# SRA_20_V8_7.net
KiCad netlist of a schematic drawn in EAGLE
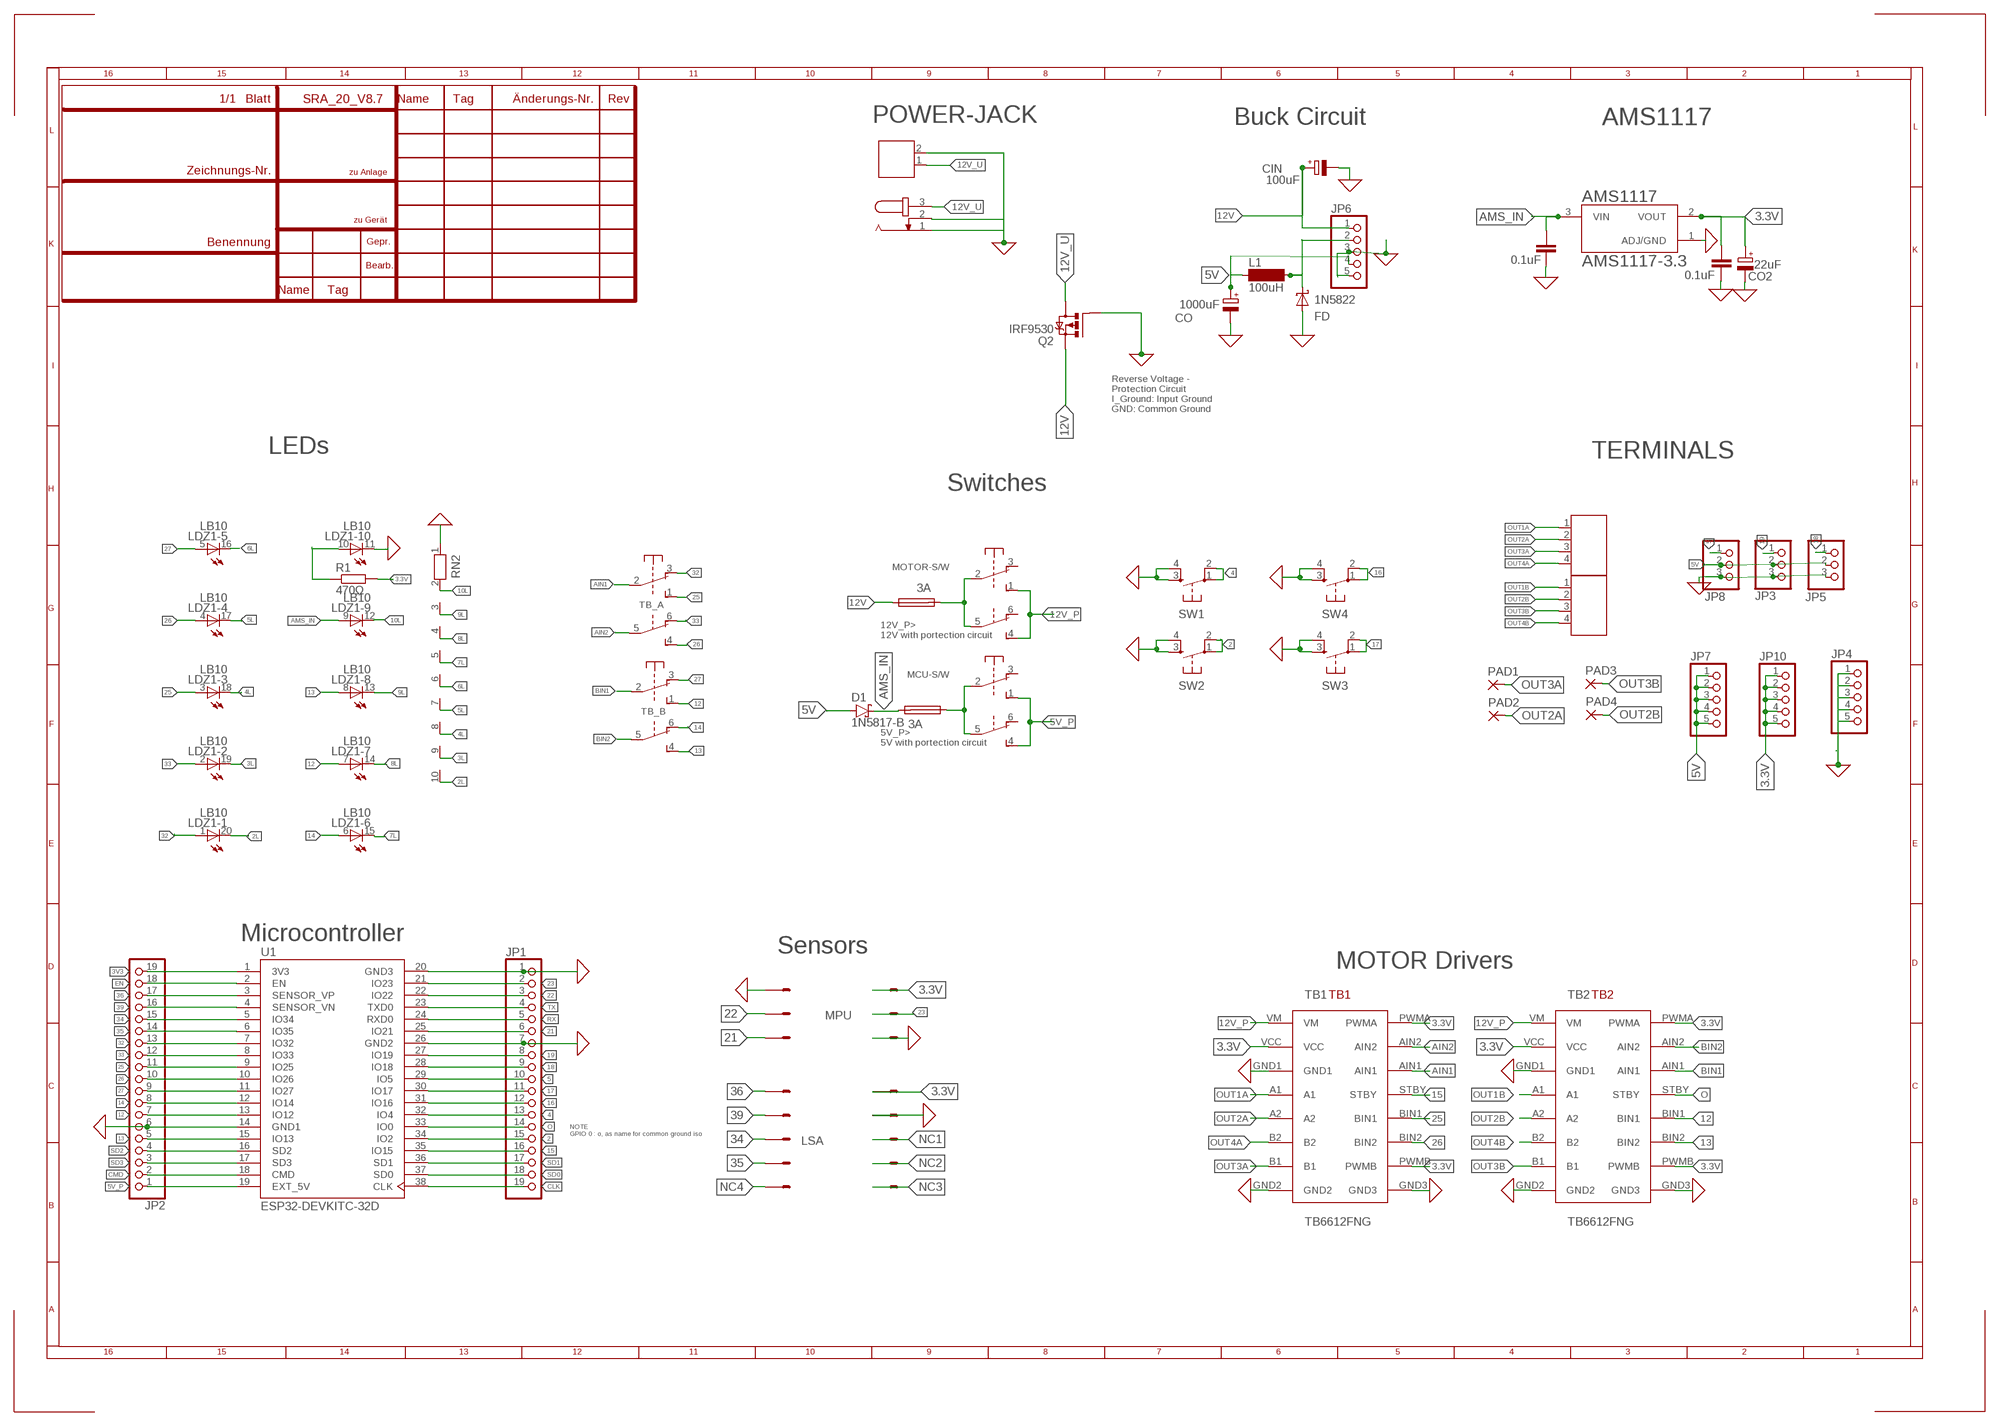
[diagram p0: schematic, sheet 1]

(export (version "E")
  (design (tool "Eeschema 10.0.6"))
  (components
    (comp (ref "12V")
      (value "691131710002")
      (footprint "eagle-import:691131710002")
      (libsource (lib "eagle-import") (part "691131710002"))
    )
    (comp (ref "AMS1117")
      (value "AMS1117-3.3")
      (footprint "eagle-import:SOT229P700X180-4N")
      (fields (field (name "MF") "Advanced Monolithic Systems"))
      (libsource (lib "eagle-import") (part "AMS1117-3.3"))
    )
    (comp (ref "CIN")
      (value "100uF")
      (footprint "eagle-import:E2,5-6")
      (libsource (lib "eagle-import") (part "CPOL-EUE2.5-6"))
    )
    (comp (ref "CIN1")
      (value "0.1uF")
      (footprint "eagle-import:C5B2.5")
      (libsource (lib "eagle-import") (part "C5/2.5"))
    )
    (comp (ref "CO")
      (value "1000uF")
      (footprint "eagle-import:E3,5-10")
      (libsource (lib "eagle-import") (part "CPOL-EUE3.5-10"))
    )
    (comp (ref "CO1")
      (value "0.1uF")
      (footprint "eagle-import:C5B2.5")
      (libsource (lib "eagle-import") (part "C5/2.5"))
    )
    (comp (ref "CO2")
      (value "22uF")
      (footprint "eagle-import:E2,5-6")
      (libsource (lib "eagle-import") (part "CPOL-EUE2.5-6"))
    )
    (comp (ref "D1")
      (value "1N5817-B")
      (footprint "eagle-import:DO41-7.6")
      (libsource (lib "eagle-import") (part "1N5817-B"))
    )
    (comp (ref "F2")
      (value "3A")
      (footprint "eagle-import:SH25")
      (fields (field (name "MF") "SCHURTER") (field (name "MPN") "0031.8211"))
      (libsource (lib "eagle-import") (part "SH25"))
    )
    (comp (ref "F3")
      (value "3A")
      (footprint "eagle-import:SH25")
      (fields (field (name "MF") "SCHURTER") (field (name "MPN") "0031.8211"))
      (libsource (lib "eagle-import") (part "SH25"))
    )
    (comp (ref "FD")
      (value "1N5822")
      (footprint "eagle-import:DIOAD2120W130L950D530P")
      (fields (field (name "MF") "ON Semiconductor"))
      (libsource (lib "eagle-import") (part "1N5822"))
    )
    (comp (ref "J1")
      (value "691131710004")
      (footprint "eagle-import:691131710004")
      (libsource (lib "eagle-import") (part "691131710004"))
    )
    (comp (ref "J2")
      (value "691131710004")
      (footprint "eagle-import:691131710004")
      (libsource (lib "eagle-import") (part "691131710004"))
    )
    (comp (ref "JP1")
      (value "PINHD-1X19")
      (footprint "eagle-import:1X19")
      (libsource (lib "eagle-import") (part "PINHD-1X19"))
    )
    (comp (ref "JP2")
      (value "PINHD-1X19")
      (footprint "eagle-import:1X19")
      (libsource (lib "eagle-import") (part "PINHD-1X19"))
    )
    (comp (ref "JP3")
      (value "PINHD-1X3")
      (footprint "eagle-import:1X03")
      (libsource (lib "eagle-import") (part "PINHD-1X3"))
    )
    (comp (ref "JP4")
      (value "PINHD-1X5")
      (footprint "eagle-import:1X05")
      (libsource (lib "eagle-import") (part "pinhead_2_PINHD-1X5"))
    )
    (comp (ref "JP5")
      (value "PINHD-1X3")
      (footprint "eagle-import:1X03")
      (libsource (lib "eagle-import") (part "PINHD-1X3"))
    )
    (comp (ref "JP6")
      (value "PINHD-1X5")
      (footprint "eagle-import:1X05")
      (libsource (lib "eagle-import") (part "PINHD-1X5"))
    )
    (comp (ref "JP7")
      (value "PINHD-1X5")
      (footprint "eagle-import:1X05")
      (libsource (lib "eagle-import") (part "pinhead_2_PINHD-1X5"))
    )
    (comp (ref "JP8")
      (value "PINHD-1X3")
      (footprint "eagle-import:1X03")
      (libsource (lib "eagle-import") (part "PINHD-1X3"))
    )
    (comp (ref "JP10")
      (value "PINHD-1X5")
      (footprint "eagle-import:1X05")
      (libsource (lib "eagle-import") (part "pinhead_2_PINHD-1X5"))
    )
    (comp (ref "L1")
      (value "100uH")
      (footprint "eagle-import:SD12K100")
      (libsource (lib "eagle-import") (part "SD12K100"))
    )
    (comp (ref "LDZ1")
      (value "LB10")
      (footprint "eagle-import:LB10")
      (libsource (lib "eagle-import") (part "LB10"))
    )
    (comp (ref "LINE-SENSOR")
      (value "057-010-1")
      (footprint "eagle-import:057-010-1")
      (libsource (lib "eagle-import") (part "057-010-1"))
    )
    (comp (ref "MCU-S/W")
      (value "9077-2")
      (footprint "eagle-import:9077-2")
      (libsource (lib "eagle-import") (part "9077-2"))
    )
    (comp (ref "MOTOR-S/W")
      (value "9077-2")
      (footprint "eagle-import:9077-2")
      (libsource (lib "eagle-import") (part "9077-2"))
    )
    (comp (ref "PAD1")
      (value "SMD2")
      (footprint "eagle-import:SMD1,27-2,54")
      (libsource (lib "eagle-import") (part "SMD2"))
    )
    (comp (ref "PAD2")
      (value "SMD2")
      (footprint "eagle-import:SMD1,27-2,54")
      (libsource (lib "eagle-import") (part "SMD2"))
    )
    (comp (ref "PAD3")
      (value "SMD2")
      (footprint "eagle-import:SMD1,27-2,54")
      (libsource (lib "eagle-import") (part "SMD2"))
    )
    (comp (ref "PAD4")
      (value "SMD2")
      (footprint "eagle-import:SMD1,27-2,54")
      (libsource (lib "eagle-import") (part "SMD2"))
    )
    (comp (ref "POWER-JACK")
      (value "JACK-PLUG1")
      (footprint "eagle-import:SPC4078")
      (libsource (lib "eagle-import") (part "JACK-PLUG1"))
    )
    (comp (ref "Q2")
      (value "IRF9530")
      (footprint "eagle-import:TO220BV")
      (libsource (lib "eagle-import") (part "IRF9530"))
    )
    (comp (ref "R1")
      (value "470Ω")
      (footprint "eagle-import:0204_7")
      (libsource (lib "eagle-import") (part "R-EU_0204/7"))
    )
    (comp (ref "RN2")
      (value "RN09")
      (footprint "eagle-import:RN-10")
      (libsource (lib "eagle-import") (part "RN09"))
    )
    (comp (ref "SW1")
      (value "DTS-6")
      (footprint "eagle-import:DTS-6")
      (libsource (lib "eagle-import") (part "DTS-6"))
    )
    (comp (ref "SW2")
      (value "DTS-6")
      (footprint "eagle-import:DTS-6")
      (libsource (lib "eagle-import") (part "DTS-6"))
    )
    (comp (ref "SW3")
      (value "DTS-6")
      (footprint "eagle-import:DTS-6")
      (libsource (lib "eagle-import") (part "DTS-6"))
    )
    (comp (ref "SW4")
      (value "DTS-6")
      (footprint "eagle-import:DTS-6")
      (libsource (lib "eagle-import") (part "DTS-6"))
    )
    (comp (ref "TB1")
      (value "TB6612FNG")
      (footprint "eagle-import:TB6612FNG")
      (libsource (lib "eagle-import") (part "TB6612FNG"))
    )
    (comp (ref "TB2")
      (value "TB6612FNG")
      (footprint "eagle-import:TB6612FNG")
      (libsource (lib "eagle-import") (part "TB6612FNG"))
    )
    (comp (ref "TB_A")
      (value "9077-2")
      (footprint "eagle-import:9077-2")
      (libsource (lib "eagle-import") (part "9077-2"))
    )
    (comp (ref "TB_B")
      (value "9077-2")
      (footprint "eagle-import:9077-2")
      (libsource (lib "eagle-import") (part "9077-2"))
    )
    (comp (ref "U1")
      (value "ESP32-DEVKITC-32D")
      (footprint "eagle-import:MODULE_ESP32-DEVKITC-32D")
      (fields (field (name "MF") "Espressif Systems"))
      (libsource (lib "eagle-import") (part "ESP32-DEVKITC-32D"))
    )
    (comp (ref "X1")
      (value "057-006-1")
      (footprint "eagle-import:057-006-1")
      (libsource (lib "eagle-import") (part "057-006-1"))
    )
  )
  (nets
    (net (code "1") (name "2") (class "Default")
      (node (ref "JP1") (pin "15") (pinfunction "15_15") (pintype "passive"))
      (node (ref "SW2") (pin "1") (pinfunction "1_1") (pintype "passive"))
      (node (ref "SW2") (pin "2") (pinfunction "2_2") (pintype "passive"))
      (node (ref "U1") (pin "34") (pinfunction "IO2_34") (pintype "bidirectional"))
    )
    (net (code "2") (name "2L") (class "Default")
      (node (ref "LDZ1") (pin "20") (pinfunction "C_20") (pintype "passive"))
      (node (ref "RN2") (pin "10") (pinfunction "10_10") (pintype "passive"))
    )
    (net (code "3") (name "3.3V") (class "Default")
      (node (ref "AMS1117") (pin "2") (pinfunction "VOUT_2") (pintype "output"))
      (node (ref "CO1") (pin "2") (pinfunction "2_2") (pintype "passive"))
      (node (ref "CO2") (pin "+") (pinfunction "+_+") (pintype "passive"))
      (node (ref "JP10") (pin "1") (pinfunction "1_1") (pintype "passive"))
      (node (ref "JP10") (pin "2") (pinfunction "2_2") (pintype "passive"))
      (node (ref "JP10") (pin "3") (pinfunction "3_3") (pintype "passive"))
      (node (ref "JP10") (pin "4") (pinfunction "4_4") (pintype "passive"))
      (node (ref "JP10") (pin "5") (pinfunction "5_5") (pintype "passive"))
      (node (ref "LINE-SENSOR") (pin "2") (pinfunction "S_2") (pintype "passive"))
      (node (ref "R1") (pin "2") (pinfunction "2_2") (pintype "passive"))
      (node (ref "TB1") (pin "PWMA") (pinfunction "PWMA_PWMA") (pintype "bidirectional"))
      (node (ref "TB1") (pin "PWMB") (pinfunction "PWMB_PWMB") (pintype "bidirectional"))
      (node (ref "TB1") (pin "VCC") (pinfunction "VCC_VCC") (pintype "bidirectional"))
      (node (ref "TB2") (pin "PWMA") (pinfunction "PWMA_PWMA") (pintype "bidirectional"))
      (node (ref "TB2") (pin "PWMB") (pinfunction "PWMB_PWMB") (pintype "bidirectional"))
      (node (ref "TB2") (pin "VCC") (pinfunction "VCC_VCC") (pintype "bidirectional"))
      (node (ref "X1") (pin "2") (pinfunction "S_2") (pintype "passive"))
    )
    (net (code "4") (name "3L") (class "Default")
      (node (ref "LDZ1") (pin "19") (pinfunction "C_19") (pintype "passive"))
      (node (ref "RN2") (pin "9") (pinfunction "9_9") (pintype "passive"))
    )
    (net (code "5") (name "3V3") (class "Default")
      (node (ref "JP2") (pin "19") (pinfunction "19_19") (pintype "passive"))
      (node (ref "U1") (pin "1") (pinfunction "3V3_1") (pintype "power_in"))
    )
    (net (code "6") (name "4") (class "Default")
      (node (ref "JP1") (pin "13") (pinfunction "13_13") (pintype "passive"))
      (node (ref "SW1") (pin "1") (pinfunction "1_1") (pintype "passive"))
      (node (ref "SW1") (pin "2") (pinfunction "2_2") (pintype "passive"))
      (node (ref "U1") (pin "32") (pinfunction "IO4_32") (pintype "bidirectional"))
    )
    (net (code "7") (name "4L") (class "Default")
      (node (ref "LDZ1") (pin "18") (pinfunction "C_18") (pintype "passive"))
      (node (ref "RN2") (pin "8") (pinfunction "8_8") (pintype "passive"))
    )
    (net (code "8") (name "5") (class "Default")
      (node (ref "JP1") (pin "10") (pinfunction "10_10") (pintype "passive"))
      (node (ref "JP8") (pin "1") (pinfunction "1_1") (pintype "passive"))
      (node (ref "U1") (pin "29") (pinfunction "IO5_29") (pintype "bidirectional"))
    )
    (net (code "9") (name "5L") (class "Default")
      (node (ref "LDZ1") (pin "17") (pinfunction "C_17") (pintype "passive"))
      (node (ref "RN2") (pin "7") (pinfunction "7_7") (pintype "passive"))
    )
    (net (code "10") (name "5V") (class "Default")
      (node (ref "CO") (pin "+") (pinfunction "+_+") (pintype "passive"))
      (node (ref "D1") (pin "A") (pinfunction "A_A") (pintype "passive"))
      (node (ref "JP3") (pin "2") (pinfunction "2_2") (pintype "passive"))
      (node (ref "JP5") (pin "2") (pinfunction "2_2") (pintype "passive"))
      (node (ref "JP6") (pin "4") (pinfunction "4_4") (pintype "passive"))
      (node (ref "JP7") (pin "1") (pinfunction "1_1") (pintype "passive"))
      (node (ref "JP7") (pin "2") (pinfunction "2_2") (pintype "passive"))
      (node (ref "JP7") (pin "3") (pinfunction "3_3") (pintype "passive"))
      (node (ref "JP7") (pin "4") (pinfunction "4_4") (pintype "passive"))
      (node (ref "JP7") (pin "5") (pinfunction "5_5") (pintype "passive"))
      (node (ref "JP8") (pin "2") (pinfunction "2_2") (pintype "passive"))
      (node (ref "L1") (pin "1") (pinfunction "1_1") (pintype "passive"))
    )
    (net (code "11") (name "5V_P") (class "Default")
      (node (ref "JP2") (pin "1") (pinfunction "1_1") (pintype "passive"))
      (node (ref "MCU-S/W") (pin "1") (pinfunction "S_1") (pintype "passive"))
      (node (ref "MCU-S/W") (pin "4") (pinfunction "S_4") (pintype "passive"))
      (node (ref "U1") (pin "19") (pinfunction "EXT_5V_19") (pintype "power_in"))
    )
    (net (code "12") (name "6L") (class "Default")
      (node (ref "LDZ1") (pin "16") (pinfunction "C_16") (pintype "passive"))
      (node (ref "RN2") (pin "6") (pinfunction "6_6") (pintype "passive"))
    )
    (net (code "13") (name "7L") (class "Default")
      (node (ref "LDZ1") (pin "15") (pinfunction "C_15") (pintype "passive"))
      (node (ref "RN2") (pin "5") (pinfunction "5_5") (pintype "passive"))
    )
    (net (code "14") (name "8L") (class "Default")
      (node (ref "LDZ1") (pin "14") (pinfunction "C_14") (pintype "passive"))
      (node (ref "RN2") (pin "4") (pinfunction "4_4") (pintype "passive"))
    )
    (net (code "15") (name "9L") (class "Default")
      (node (ref "LDZ1") (pin "13") (pinfunction "C_13") (pintype "passive"))
      (node (ref "RN2") (pin "3") (pinfunction "3_3") (pintype "passive"))
    )
    (net (code "16") (name "10L") (class "Default")
      (node (ref "LDZ1") (pin "12") (pinfunction "C_12") (pintype "passive"))
      (node (ref "RN2") (pin "2") (pinfunction "2_2") (pintype "passive"))
    )
    (net (code "17") (name "12") (class "Default")
      (node (ref "JP2") (pin "7") (pinfunction "7_7") (pintype "passive"))
      (node (ref "LDZ1") (pin "7") (pinfunction "A_7") (pintype "passive"))
      (node (ref "TB2") (pin "BIN1") (pinfunction "BIN1_BIN1") (pintype "bidirectional"))
      (node (ref "TB_B") (pin "1") (pinfunction "S_1") (pintype "passive"))
      (node (ref "U1") (pin "13") (pinfunction "IO12_13") (pintype "bidirectional"))
    )
    (net (code "18") (name "12V") (class "Default")
      (node (ref "CIN") (pin "+") (pinfunction "+_+") (pintype "passive"))
      (node (ref "F3") (pin "1") (pinfunction "1_1") (pintype "passive"))
      (node (ref "JP6") (pin "1") (pinfunction "1_1") (pintype "passive"))
      (node (ref "Q2") (pin "S") (pinfunction "S_S") (pintype "passive"))
    )
    (net (code "19") (name "12V_P") (class "Default")
      (node (ref "MOTOR-S/W") (pin "1") (pinfunction "S_1") (pintype "passive"))
      (node (ref "MOTOR-S/W") (pin "4") (pinfunction "S_4") (pintype "passive"))
      (node (ref "TB1") (pin "VM") (pinfunction "VM_VM") (pintype "bidirectional"))
      (node (ref "TB2") (pin "VM") (pinfunction "VM_VM") (pintype "bidirectional"))
    )
    (net (code "20") (name "12V_U") (class "Default")
      (node (ref "12V") (pin "1") (pinfunction "1_1") (pintype "passive"))
      (node (ref "POWER-JACK") (pin "3") (pinfunction "3_3") (pintype "passive"))
      (node (ref "Q2") (pin "D") (pinfunction "D_D") (pintype "passive"))
    )
    (net (code "21") (name "13") (class "Default")
      (node (ref "JP2") (pin "5") (pinfunction "5_5") (pintype "passive"))
      (node (ref "LDZ1") (pin "8") (pinfunction "A_8") (pintype "passive"))
      (node (ref "TB2") (pin "BIN2") (pinfunction "BIN2_BIN2") (pintype "bidirectional"))
      (node (ref "TB_B") (pin "4") (pinfunction "S_4") (pintype "passive"))
      (node (ref "U1") (pin "15") (pinfunction "IO13_15") (pintype "bidirectional"))
    )
    (net (code "22") (name "14") (class "Default")
      (node (ref "JP2") (pin "8") (pinfunction "8_8") (pintype "passive"))
      (node (ref "LDZ1") (pin "6") (pinfunction "A_6") (pintype "passive"))
      (node (ref "TB_B") (pin "6") (pinfunction "O_6") (pintype "passive"))
      (node (ref "U1") (pin "12") (pinfunction "IO14_12") (pintype "bidirectional"))
    )
    (net (code "23") (name "15") (class "Default")
      (node (ref "JP1") (pin "16") (pinfunction "16_16") (pintype "passive"))
      (node (ref "TB1") (pin "STBY") (pinfunction "STBY_STBY") (pintype "bidirectional"))
      (node (ref "U1") (pin "35") (pinfunction "IO15_35") (pintype "bidirectional"))
    )
    (net (code "24") (name "16") (class "Default")
      (node (ref "JP1") (pin "12") (pinfunction "12_12") (pintype "passive"))
      (node (ref "SW4") (pin "1") (pinfunction "1_1") (pintype "passive"))
      (node (ref "SW4") (pin "2") (pinfunction "2_2") (pintype "passive"))
      (node (ref "U1") (pin "31") (pinfunction "IO16_31") (pintype "bidirectional"))
    )
    (net (code "25") (name "17") (class "Default")
      (node (ref "JP1") (pin "11") (pinfunction "11_11") (pintype "passive"))
      (node (ref "SW3") (pin "1") (pinfunction "1_1") (pintype "passive"))
      (node (ref "SW3") (pin "2") (pinfunction "2_2") (pintype "passive"))
      (node (ref "U1") (pin "30") (pinfunction "IO17_30") (pintype "bidirectional"))
    )
    (net (code "26") (name "18") (class "Default")
      (node (ref "JP1") (pin "9") (pinfunction "9_9") (pintype "passive"))
      (node (ref "JP5") (pin "1") (pinfunction "1_1") (pintype "passive"))
      (node (ref "U1") (pin "28") (pinfunction "IO18_28") (pintype "bidirectional"))
    )
    (net (code "27") (name "19") (class "Default")
      (node (ref "JP1") (pin "8") (pinfunction "8_8") (pintype "passive"))
      (node (ref "JP3") (pin "1") (pinfunction "1_1") (pintype "passive"))
      (node (ref "U1") (pin "27") (pinfunction "IO19_27") (pintype "bidirectional"))
    )
    (net (code "28") (name "21") (class "Default")
      (node (ref "JP1") (pin "6") (pinfunction "6_6") (pintype "passive"))
      (node (ref "U1") (pin "25") (pinfunction "IO21_25") (pintype "bidirectional"))
      (node (ref "X1") (pin "5") (pinfunction "S_5") (pintype "passive"))
    )
    (net (code "29") (name "22") (class "Default")
      (node (ref "JP1") (pin "3") (pinfunction "3_3") (pintype "passive"))
      (node (ref "U1") (pin "22") (pinfunction "IO22_22") (pintype "bidirectional"))
      (node (ref "X1") (pin "3") (pinfunction "S_3") (pintype "passive"))
    )
    (net (code "30") (name "23") (class "Default")
      (node (ref "JP1") (pin "2") (pinfunction "2_2") (pintype "passive"))
      (node (ref "U1") (pin "21") (pinfunction "IO23_21") (pintype "bidirectional"))
      (node (ref "X1") (pin "4") (pinfunction "S_4") (pintype "passive"))
    )
    (net (code "31") (name "25") (class "Default")
      (node (ref "JP2") (pin "11") (pinfunction "11_11") (pintype "passive"))
      (node (ref "LDZ1") (pin "3") (pinfunction "A_3") (pintype "passive"))
      (node (ref "TB1") (pin "BIN1") (pinfunction "BIN1_BIN1") (pintype "bidirectional"))
      (node (ref "TB_A") (pin "1") (pinfunction "S_1") (pintype "passive"))
      (node (ref "U1") (pin "9") (pinfunction "IO25_9") (pintype "bidirectional"))
    )
    (net (code "32") (name "26") (class "Default")
      (node (ref "JP2") (pin "10") (pinfunction "10_10") (pintype "passive"))
      (node (ref "LDZ1") (pin "4") (pinfunction "A_4") (pintype "passive"))
      (node (ref "TB1") (pin "BIN2") (pinfunction "BIN2_BIN2") (pintype "bidirectional"))
      (node (ref "TB_A") (pin "4") (pinfunction "S_4") (pintype "passive"))
      (node (ref "U1") (pin "10") (pinfunction "IO26_10") (pintype "bidirectional"))
    )
    (net (code "33") (name "27") (class "Default")
      (node (ref "JP2") (pin "9") (pinfunction "9_9") (pintype "passive"))
      (node (ref "LDZ1") (pin "5") (pinfunction "A_5") (pintype "passive"))
      (node (ref "TB_B") (pin "3") (pinfunction "O_3") (pintype "passive"))
      (node (ref "U1") (pin "11") (pinfunction "IO27_11") (pintype "bidirectional"))
    )
    (net (code "34") (name "32") (class "Default")
      (node (ref "JP2") (pin "13") (pinfunction "13_13") (pintype "passive"))
      (node (ref "LDZ1") (pin "1") (pinfunction "A_1") (pintype "passive"))
      (node (ref "TB_A") (pin "3") (pinfunction "O_3") (pintype "passive"))
      (node (ref "U1") (pin "7") (pinfunction "IO32_7") (pintype "bidirectional"))
    )
    (net (code "35") (name "33") (class "Default")
      (node (ref "JP2") (pin "12") (pinfunction "12_12") (pintype "passive"))
      (node (ref "LDZ1") (pin "2") (pinfunction "A_2") (pintype "passive"))
      (node (ref "TB_A") (pin "6") (pinfunction "O_6") (pintype "passive"))
      (node (ref "U1") (pin "8") (pinfunction "IO33_8") (pintype "bidirectional"))
    )
    (net (code "36") (name "34") (class "Default")
      (node (ref "JP2") (pin "15") (pinfunction "15_15") (pintype "passive"))
      (node (ref "LINE-SENSOR") (pin "5") (pinfunction "S_5") (pintype "passive"))
      (node (ref "U1") (pin "5") (pinfunction "IO34_5") (pintype "bidirectional"))
    )
    (net (code "37") (name "35") (class "Default")
      (node (ref "JP2") (pin "14") (pinfunction "14_14") (pintype "passive"))
      (node (ref "LINE-SENSOR") (pin "7") (pinfunction "S_7") (pintype "passive"))
      (node (ref "U1") (pin "6") (pinfunction "IO35_6") (pintype "bidirectional"))
    )
    (net (code "38") (name "36") (class "Default")
      (node (ref "JP2") (pin "17") (pinfunction "17_17") (pintype "passive"))
      (node (ref "LINE-SENSOR") (pin "1") (pinfunction "S_1") (pintype "passive"))
      (node (ref "U1") (pin "3") (pinfunction "SENSOR_VP_3") (pintype "input"))
    )
    (net (code "39") (name "39") (class "Default")
      (node (ref "JP2") (pin "16") (pinfunction "16_16") (pintype "passive"))
      (node (ref "LINE-SENSOR") (pin "3") (pinfunction "S_3") (pintype "passive"))
      (node (ref "U1") (pin "4") (pinfunction "SENSOR_VN_4") (pintype "input"))
    )
    (net (code "40") (name "AIN1") (class "Default")
      (node (ref "TB1") (pin "AIN1") (pinfunction "AIN1_AIN1") (pintype "bidirectional"))
      (node (ref "TB_A") (pin "2") (pinfunction "P_2") (pintype "passive"))
    )
    (net (code "41") (name "AIN2") (class "Default")
      (node (ref "TB1") (pin "AIN2") (pinfunction "AIN2_AIN2") (pintype "bidirectional"))
      (node (ref "TB_A") (pin "5") (pinfunction "P_5") (pintype "passive"))
    )
    (net (code "42") (name "AMS_IN") (class "Default")
      (node (ref "AMS1117") (pin "3") (pinfunction "VIN_3") (pintype "input"))
      (node (ref "CIN1") (pin "2") (pinfunction "2_2") (pintype "passive"))
      (node (ref "D1") (pin "C") (pinfunction "C_C") (pintype "passive"))
      (node (ref "F2") (pin "2") (pinfunction "2_2") (pintype "passive"))
      (node (ref "LDZ1") (pin "9") (pinfunction "A_9") (pintype "passive"))
    )
    (net (code "43") (name "BIN1") (class "Default")
      (node (ref "TB2") (pin "AIN1") (pinfunction "AIN1_AIN1") (pintype "bidirectional"))
      (node (ref "TB_B") (pin "2") (pinfunction "P_2") (pintype "passive"))
    )
    (net (code "44") (name "BIN2") (class "Default")
      (node (ref "TB2") (pin "AIN2") (pinfunction "AIN2_AIN2") (pintype "bidirectional"))
      (node (ref "TB_B") (pin "5") (pinfunction "P_5") (pintype "passive"))
    )
    (net (code "45") (name "CLK") (class "Default")
      (node (ref "JP1") (pin "19") (pinfunction "19_19") (pintype "passive"))
      (node (ref "U1") (pin "38") (pinfunction "CLK_38") (pintype "input"))
    )
    (net (code "46") (name "CMD") (class "Default")
      (node (ref "JP2") (pin "2") (pinfunction "2_2") (pintype "passive"))
      (node (ref "U1") (pin "18") (pinfunction "CMD_18") (pintype "bidirectional"))
    )
    (net (code "47") (name "EN") (class "Default")
      (node (ref "JP2") (pin "18") (pinfunction "18_18") (pintype "passive"))
      (node (ref "U1") (pin "2") (pinfunction "EN_2") (pintype "input"))
    )
    (net (code "48") (name "GND") (class "Default")
      (node (ref "12V") (pin "2") (pinfunction "2_2") (pintype "passive"))
      (node (ref "AMS1117") (pin "1") (pinfunction "ADJ/GND_1") (pintype "power_in"))
      (node (ref "CIN") (pin "-") (pinfunction "-_-") (pintype "passive"))
      (node (ref "CIN1") (pin "1") (pinfunction "1_1") (pintype "passive"))
      (node (ref "CO") (pin "-") (pinfunction "-_-") (pintype "passive"))
      (node (ref "CO1") (pin "1") (pinfunction "1_1") (pintype "passive"))
      (node (ref "CO2") (pin "-") (pinfunction "-_-") (pintype "passive"))
      (node (ref "FD") (pin "A") (pinfunction "A_A") (pintype "passive"))
      (node (ref "JP1") (pin "1") (pinfunction "1_1") (pintype "passive"))
      (node (ref "JP1") (pin "7") (pinfunction "7_7") (pintype "passive"))
      (node (ref "JP2") (pin "6") (pinfunction "6_6") (pintype "passive"))
      (node (ref "JP3") (pin "3") (pinfunction "3_3") (pintype "passive"))
      (node (ref "JP4") (pin "1") (pinfunction "1_1") (pintype "passive"))
      (node (ref "JP4") (pin "2") (pinfunction "2_2") (pintype "passive"))
      (node (ref "JP4") (pin "3") (pinfunction "3_3") (pintype "passive"))
      (node (ref "JP4") (pin "4") (pinfunction "4_4") (pintype "passive"))
      (node (ref "JP4") (pin "5") (pinfunction "5_5") (pintype "passive"))
      (node (ref "JP5") (pin "3") (pinfunction "3_3") (pintype "passive"))
      (node (ref "JP6") (pin "3") (pinfunction "3_3") (pintype "passive"))
      (node (ref "JP6") (pin "5") (pinfunction "5_5") (pintype "passive"))
      (node (ref "JP8") (pin "3") (pinfunction "3_3") (pintype "passive"))
      (node (ref "LDZ1") (pin "11") (pinfunction "C_11") (pintype "passive"))
      (node (ref "LINE-SENSOR") (pin "4") (pinfunction "S_4") (pintype "passive"))
      (node (ref "POWER-JACK") (pin "1") (pinfunction "1_1") (pintype "passive"))
      (node (ref "POWER-JACK") (pin "2") (pinfunction "2_2") (pintype "passive"))
      (node (ref "Q2") (pin "G") (pinfunction "G_G") (pintype "passive"))
      (node (ref "RN2") (pin "1") (pinfunction "1_1") (pintype "passive"))
      (node (ref "SW1") (pin "3") (pinfunction "3_3") (pintype "passive"))
      (node (ref "SW1") (pin "4") (pinfunction "4_4") (pintype "passive"))
      (node (ref "SW2") (pin "3") (pinfunction "3_3") (pintype "passive"))
      (node (ref "SW2") (pin "4") (pinfunction "4_4") (pintype "passive"))
      (node (ref "SW3") (pin "3") (pinfunction "3_3") (pintype "passive"))
      (node (ref "SW3") (pin "4") (pinfunction "4_4") (pintype "passive"))
      (node (ref "SW4") (pin "3") (pinfunction "3_3") (pintype "passive"))
      (node (ref "SW4") (pin "4") (pinfunction "4_4") (pintype "passive"))
      (node (ref "TB1") (pin "GND1") (pinfunction "GND1_GND1") (pintype "bidirectional"))
      (node (ref "TB1") (pin "GND2") (pinfunction "GND2_GND2") (pintype "bidirectional"))
      (node (ref "TB1") (pin "GND3") (pinfunction "GND3_GND3") (pintype "bidirectional"))
      (node (ref "TB2") (pin "GND1") (pinfunction "GND1_GND1") (pintype "bidirectional"))
      (node (ref "TB2") (pin "GND2") (pinfunction "GND2_GND2") (pintype "bidirectional"))
      (node (ref "TB2") (pin "GND3") (pinfunction "GND3_GND3") (pintype "bidirectional"))
      (node (ref "U1") (pin "14") (pinfunction "GND1_14") (pintype "power_in"))
      (node (ref "U1") (pin "20") (pinfunction "GND3_20") (pintype "power_in"))
      (node (ref "U1") (pin "26") (pinfunction "GND2_26") (pintype "power_in"))
      (node (ref "X1") (pin "1") (pinfunction "S_1") (pintype "passive"))
      (node (ref "X1") (pin "6") (pinfunction "S_6") (pintype "passive"))
    )
    (net (code "49") (name "NC1") (class "Default")
      (node (ref "LINE-SENSOR") (pin "6") (pinfunction "S_6") (pintype "passive"))
    )
    (net (code "50") (name "NC2") (class "Default")
      (node (ref "LINE-SENSOR") (pin "8") (pinfunction "S_8") (pintype "passive"))
    )
    (net (code "51") (name "NC3") (class "Default")
      (node (ref "LINE-SENSOR") (pin "10") (pinfunction "S_10") (pintype "passive"))
    )
    (net (code "52") (name "NC4") (class "Default")
      (node (ref "LINE-SENSOR") (pin "9") (pinfunction "S_9") (pintype "passive"))
    )
    (net (code "53") (name "Net-(FD-PadC)") (class "Default")
      (node (ref "FD") (pin "C") (pinfunction "C_C") (pintype "passive"))
      (node (ref "JP6") (pin "2") (pinfunction "2_2") (pintype "passive"))
      (node (ref "L1") (pin "2") (pinfunction "2_2") (pintype "passive"))
    )
    (net (code "54") (name "Net-(LDZ1B-A)") (class "Default")
      (node (ref "LDZ1") (pin "10") (pinfunction "A_10") (pintype "passive"))
      (node (ref "R1") (pin "1") (pinfunction "1_1") (pintype "passive"))
    )
    (net (code "55") (name "Net-(MCU-S/WA-P)") (class "Default")
      (node (ref "F2") (pin "1") (pinfunction "1_1") (pintype "passive"))
      (node (ref "MCU-S/W") (pin "2") (pinfunction "P_2") (pintype "passive"))
      (node (ref "MCU-S/W") (pin "5") (pinfunction "P_5") (pintype "passive"))
    )
    (net (code "56") (name "Net-(MOTOR-S/WA-P)") (class "Default")
      (node (ref "F3") (pin "2") (pinfunction "2_2") (pintype "passive"))
      (node (ref "MOTOR-S/W") (pin "2") (pinfunction "P_2") (pintype "passive"))
      (node (ref "MOTOR-S/W") (pin "5") (pinfunction "P_5") (pintype "passive"))
    )
    (net (code "57") (name "O") (class "Default")
      (node (ref "JP1") (pin "14") (pinfunction "14_14") (pintype "passive"))
      (node (ref "TB2") (pin "STBY") (pinfunction "STBY_STBY") (pintype "bidirectional"))
      (node (ref "U1") (pin "33") (pinfunction "IO0_33") (pintype "bidirectional"))
    )
    (net (code "58") (name "OUT1A") (class "Default")
      (node (ref "J1") (pin "1") (pinfunction "1_1") (pintype "passive"))
      (node (ref "TB1") (pin "A1") (pinfunction "A1_A1") (pintype "bidirectional"))
    )
    (net (code "59") (name "OUT1B") (class "Default")
      (node (ref "J2") (pin "1") (pinfunction "1_1") (pintype "passive"))
      (node (ref "TB2") (pin "A1") (pinfunction "A1_A1") (pintype "bidirectional"))
    )
    (net (code "60") (name "OUT2A") (class "Default")
      (node (ref "J1") (pin "2") (pinfunction "2_2") (pintype "passive"))
      (node (ref "PAD2") (pin "1") (pinfunction "P_1") (pintype "passive"))
      (node (ref "TB1") (pin "A2") (pinfunction "A2_A2") (pintype "bidirectional"))
    )
    (net (code "61") (name "OUT2B") (class "Default")
      (node (ref "J2") (pin "2") (pinfunction "2_2") (pintype "passive"))
      (node (ref "PAD4") (pin "1") (pinfunction "P_1") (pintype "passive"))
      (node (ref "TB2") (pin "A2") (pinfunction "A2_A2") (pintype "bidirectional"))
    )
    (net (code "62") (name "OUT3A") (class "Default")
      (node (ref "J1") (pin "3") (pinfunction "3_3") (pintype "passive"))
      (node (ref "PAD1") (pin "1") (pinfunction "P_1") (pintype "passive"))
      (node (ref "TB1") (pin "B1") (pinfunction "B1_B1") (pintype "bidirectional"))
    )
    (net (code "63") (name "OUT3B") (class "Default")
      (node (ref "J2") (pin "3") (pinfunction "3_3") (pintype "passive"))
      (node (ref "PAD3") (pin "1") (pinfunction "P_1") (pintype "passive"))
      (node (ref "TB2") (pin "B1") (pinfunction "B1_B1") (pintype "bidirectional"))
    )
    (net (code "64") (name "OUT4A") (class "Default")
      (node (ref "J1") (pin "4") (pinfunction "4_4") (pintype "passive"))
      (node (ref "TB1") (pin "B2") (pinfunction "B2_B2") (pintype "bidirectional"))
    )
    (net (code "65") (name "OUT4B") (class "Default")
      (node (ref "J2") (pin "4") (pinfunction "4_4") (pintype "passive"))
      (node (ref "TB2") (pin "B2") (pinfunction "B2_B2") (pintype "bidirectional"))
    )
    (net (code "66") (name "RX") (class "Default")
      (node (ref "JP1") (pin "5") (pinfunction "5_5") (pintype "passive"))
      (node (ref "U1") (pin "24") (pinfunction "RXD0_24") (pintype "input"))
    )
    (net (code "67") (name "SD0") (class "Default")
      (node (ref "JP1") (pin "18") (pinfunction "18_18") (pintype "passive"))
      (node (ref "U1") (pin "37") (pinfunction "SD0_37") (pintype "bidirectional"))
    )
    (net (code "68") (name "SD1") (class "Default")
      (node (ref "JP1") (pin "17") (pinfunction "17_17") (pintype "passive"))
      (node (ref "U1") (pin "36") (pinfunction "SD1_36") (pintype "bidirectional"))
    )
    (net (code "69") (name "SD2") (class "Default")
      (node (ref "JP2") (pin "4") (pinfunction "4_4") (pintype "passive"))
      (node (ref "U1") (pin "16") (pinfunction "SD2_16") (pintype "bidirectional"))
    )
    (net (code "70") (name "SD3") (class "Default")
      (node (ref "JP2") (pin "3") (pinfunction "3_3") (pintype "passive"))
      (node (ref "U1") (pin "17") (pinfunction "SD3_17") (pintype "bidirectional"))
    )
    (net (code "71") (name "TX") (class "Default")
      (node (ref "JP1") (pin "4") (pinfunction "4_4") (pintype "passive"))
      (node (ref "U1") (pin "23") (pinfunction "TXD0_23") (pintype "output"))
    )
    (net (code "72") (name "unconnected-(MCU-S/WA-O-Pad3)") (class "Default")
      (node (ref "MCU-S/W") (pin "3") (pinfunction "O_3") (pintype "passive"))
    )
    (net (code "73") (name "unconnected-(MCU-S/WB-O-Pad6)") (class "Default")
      (node (ref "MCU-S/W") (pin "6") (pinfunction "O_6") (pintype "passive"))
    )
    (net (code "74") (name "unconnected-(MOTOR-S/WA-O-Pad3)") (class "Default")
      (node (ref "MOTOR-S/W") (pin "3") (pinfunction "O_3") (pintype "passive"))
    )
    (net (code "75") (name "unconnected-(MOTOR-S/WB-O-Pad6)") (class "Default")
      (node (ref "MOTOR-S/W") (pin "6") (pinfunction "O_6") (pintype "passive"))
    )
  )
)
